# Clock.net
KiCad netlist of a schematic drawn in Altium Designer
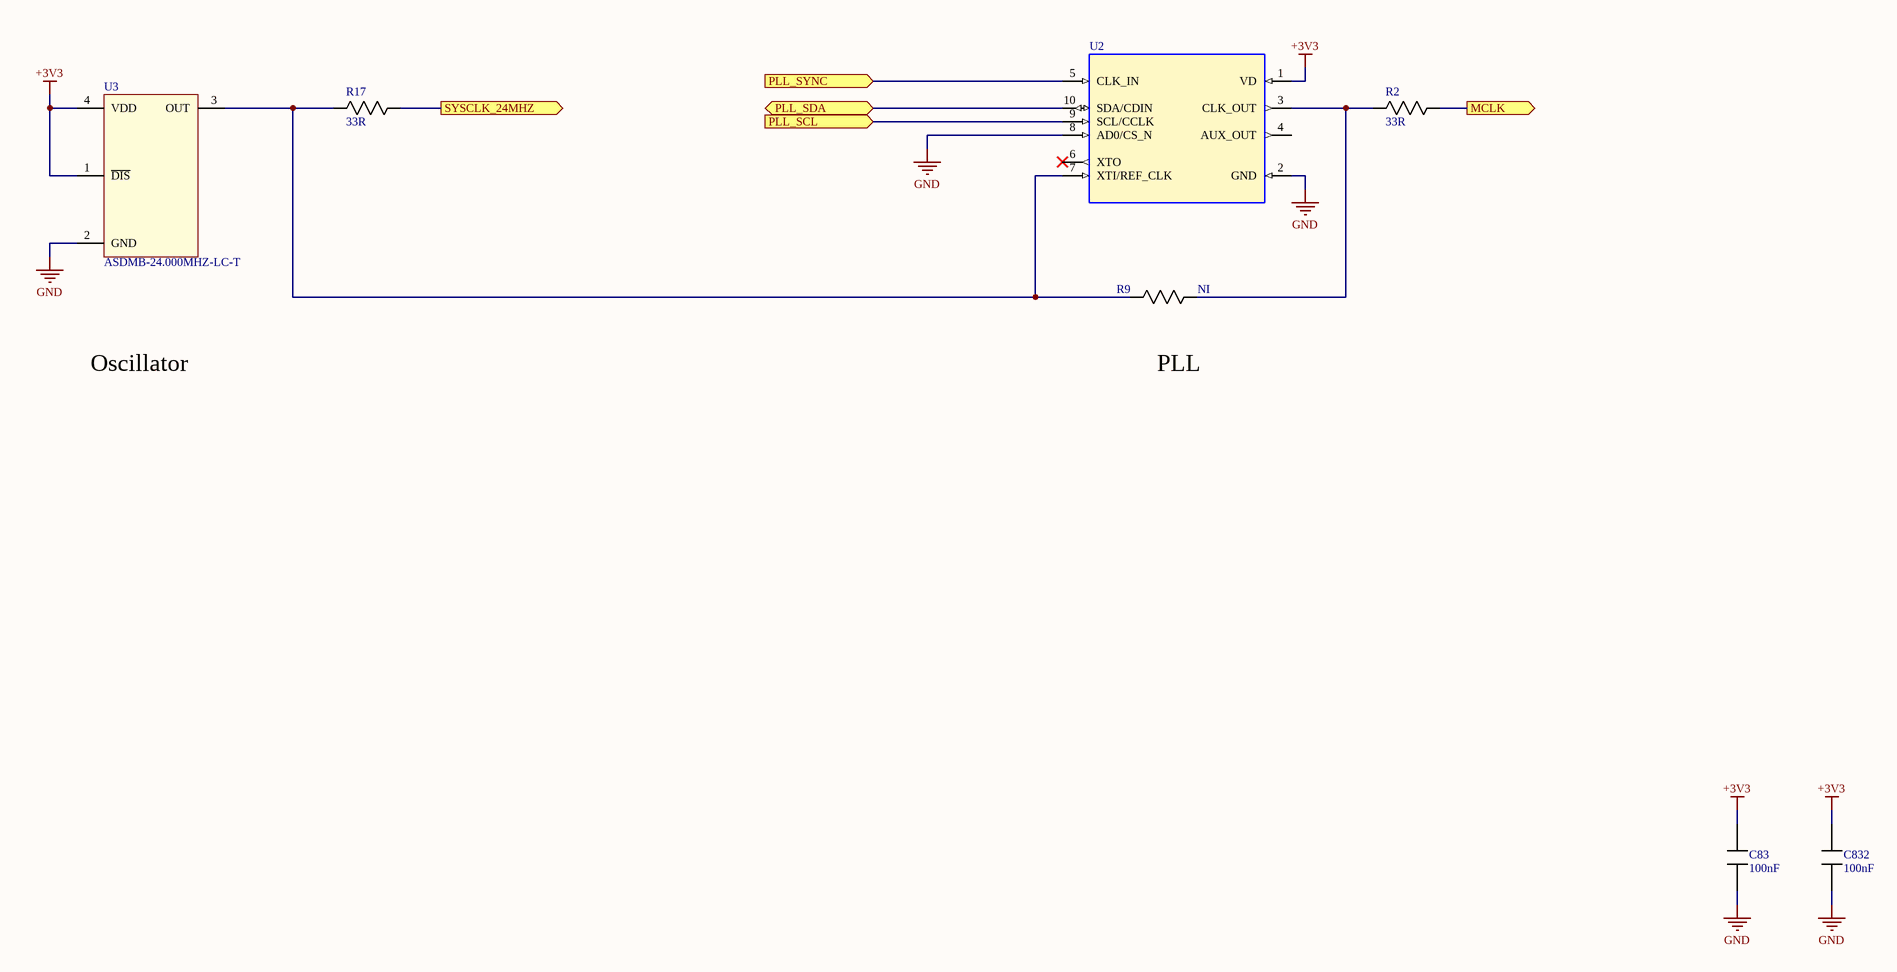
[diagram p0: Clock.SchDoc]

(export (version "E")
  (design (tool "Eeschema 10.0.6"))
  (components
    (comp (ref "C83")
      (value "100nF")
      (footprint "0603")
      (description "Capacitor")
      (libsource (lib "INTER_2014") (part "Capacitor"))
    )
    (comp (ref "C832")
      (value "100nF")
      (footprint "0603")
      (description "Capacitor")
      (libsource (lib "INTER_2014") (part "Capacitor"))
    )
    (comp (ref "R2")
      (value "33R")
      (footprint "0603")
      (description "Resistor")
      (libsource (lib "INTER_2014") (part "Resistor"))
    )
    (comp (ref "R9")
      (value "Resistor")
      (footprint "0603")
      (fields (field (name "NI") "NI"))
      (libsource (lib "INTER_2014") (part "Resistor"))
    )
    (comp (ref "R17")
      (value "33R")
      (footprint "0603")
      (description "Resistor")
      (libsource (lib "INTER_2014") (part "Resistor"))
    )
    (comp (ref "U2")
      (value "CS2100_CP")
      (footprint "MSOP10")
      (description "Fractional-N Clock Multiplier, Crystal Reference, MSOP10")
      (fields (field (name "MFG") "Cirrus Logic"))
      (libsource (lib "INTER_2014") (part "CS2100_CP"))
    )
    (comp (ref "U3")
      (value "OSC_ASDMB")
      (footprint "OSC_ADSMB")
      (description "Oscillator; 1V8 to 3V3")
      (fields (field (name "MFG") "Abracon") (field (name "MFG_PN") "ASDMB-24.000MHZ-LC-T"))
      (libsource (lib "INTER_2014") (part "OSC_ASDMB"))
    )
  )
  (nets
    (net (code "1") (name "+3V3") (class "Default")
      (node (ref "C83") (pin "1") (pintype "passive"))
      (node (ref "C832") (pin "1") (pintype "passive"))
      (node (ref "U2") (pin "1") (pinfunction "VD_1") (pintype "input"))
      (node (ref "U3") (pin "1") (pinfunction "~{DIS}_1") (pintype "passive"))
      (node (ref "U3") (pin "4") (pinfunction "VDD_4") (pintype "passive"))
    )
    (net (code "2") (name "/MCLK") (class "Default") (node (ref "R2") (pin "2") (pintype "passive")))
    (net (code "3") (name "/PLL_SCL") (class "Default")
      (node (ref "U2") (pin "9") (pinfunction "SCL/CCLK_9") (pintype "input"))
    )
    (net (code "4") (name "/PLL_SDA") (class "Default")
      (node (ref "U2") (pin "10") (pinfunction "SDA/CDIN_10") (pintype "bidirectional"))
    )
    (net (code "5") (name "/PLL_SYNC") (class "Default")
      (node (ref "U2") (pin "5") (pinfunction "CLK_IN_5") (pintype "input"))
    )
    (net (code "6") (name "/SYSCLK_24MHZ") (class "Default") (node (ref "R17") (pin "2") (pintype "passive")))
    (net (code "7") (name "GND") (class "Default")
      (node (ref "C83") (pin "2") (pintype "passive"))
      (node (ref "C832") (pin "2") (pintype "passive"))
      (node (ref "U2") (pin "2") (pinfunction "GND_2") (pintype "input"))
      (node (ref "U2") (pin "8") (pinfunction "AD0/CS_N_8") (pintype "input"))
      (node (ref "U3") (pin "2") (pinfunction "GND_2") (pintype "passive"))
    )
    (net (code "8") (name "Net-(U2-CLK_OUT)") (class "Default")
      (node (ref "R2") (pin "1") (pintype "passive"))
      (node (ref "R9") (pin "2") (pintype "passive"))
      (node (ref "U2") (pin "3") (pinfunction "CLK_OUT_3") (pintype "output"))
    )
    (net (code "9") (name "Net-(U2-XTI{slash}REF_CLK)") (class "Default")
      (node (ref "R17") (pin "1") (pintype "passive"))
      (node (ref "R9") (pin "1") (pintype "passive"))
      (node (ref "U2") (pin "7") (pinfunction "XTI/REF_CLK_7") (pintype "input"))
      (node (ref "U3") (pin "3") (pinfunction "OUT_3") (pintype "passive"))
    )
    (net (code "10") (name "unconnected-(U2-AUX_OUT-Pad4)") (class "Default")
      (node (ref "U2") (pin "4") (pinfunction "AUX_OUT_4") (pintype "output"))
    )
    (net (code "11") (name "unconnected-(U2-XTO-Pad6)") (class "Default")
      (node (ref "U2") (pin "6") (pinfunction "XTO_6") (pintype "output+no_connect"))
    )
  )
)
